# PERIPHERALS.net
KiCad netlist of a schematic drawn in Altium Designer
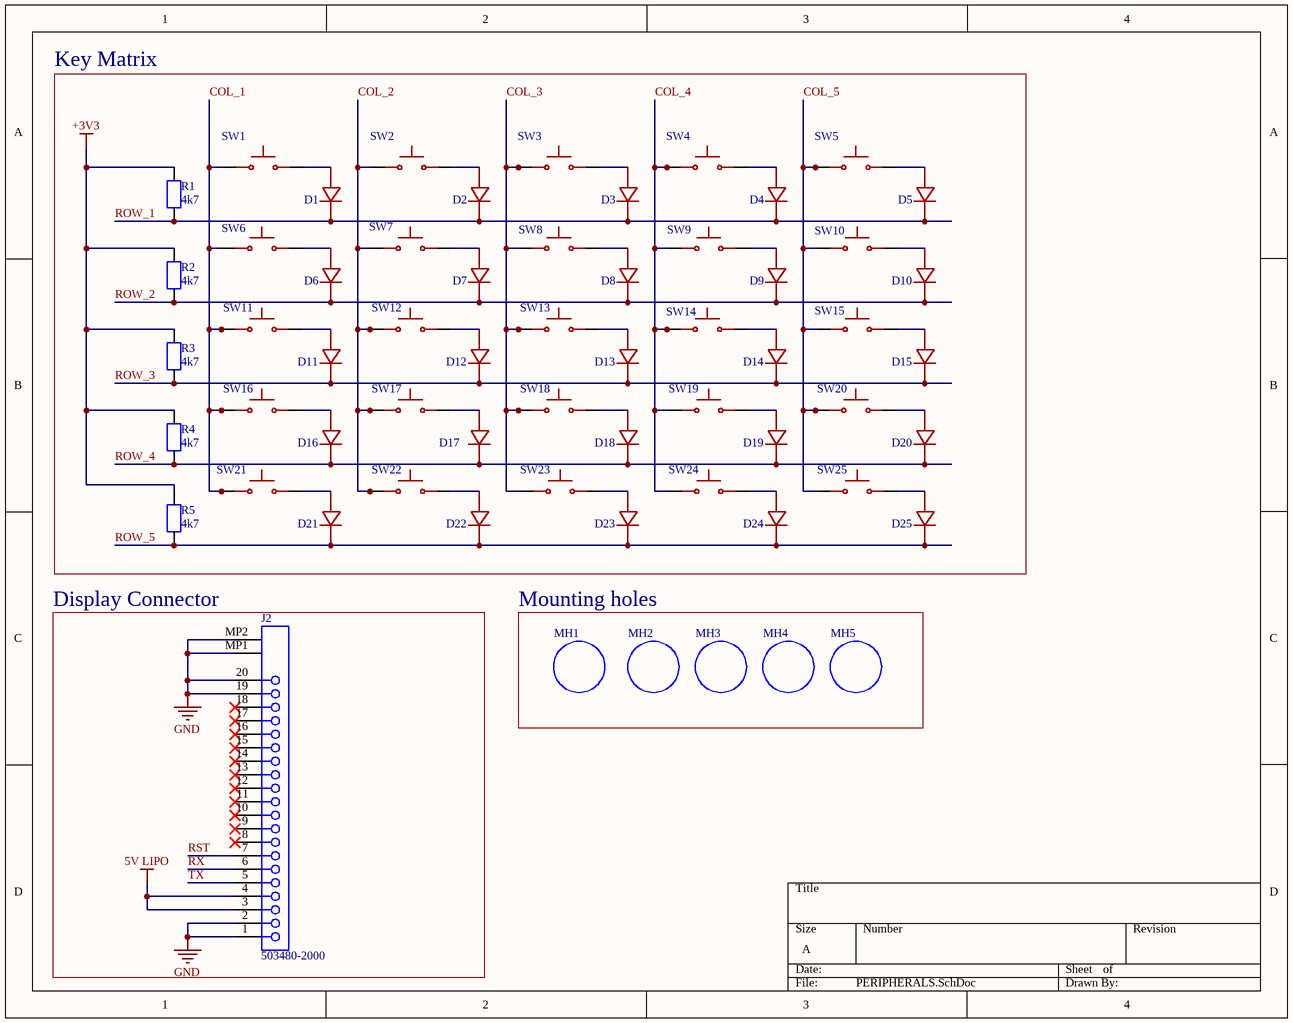
[diagram p0: PERIPHERALS.SchDoc]

(export (version "E")
  (design (tool "Eeschema 10.0.6"))
  (components
    (comp (ref "D1")
      (value "SOD-323")
      (footprint "SOD-323")
      (description "1N4148WS")
      (libsource (lib "schematiclibrary") (part "SOD-323"))
    )
    (comp (ref "D2")
      (value "SOD-323")
      (footprint "SOD-323")
      (description "1N4148WS")
      (libsource (lib "schematiclibrary") (part "SOD-323"))
    )
    (comp (ref "D3")
      (value "SOD-323")
      (footprint "SOD-323")
      (description "1N4148WS")
      (libsource (lib "schematiclibrary") (part "SOD-323"))
    )
    (comp (ref "D4")
      (value "SOD-323")
      (footprint "SOD-323")
      (description "1N4148WS")
      (libsource (lib "schematiclibrary") (part "SOD-323"))
    )
    (comp (ref "D5")
      (value "SOD-323")
      (footprint "SOD-323")
      (description "1N4148WS")
      (libsource (lib "schematiclibrary") (part "SOD-323"))
    )
    (comp (ref "D6")
      (value "SOD-323")
      (footprint "SOD-323")
      (description "1N4148WS")
      (libsource (lib "schematiclibrary") (part "SOD-323"))
    )
    (comp (ref "D7")
      (value "SOD-323")
      (footprint "SOD-323")
      (description "1N4148WS")
      (libsource (lib "schematiclibrary") (part "SOD-323"))
    )
    (comp (ref "D8")
      (value "SOD-323")
      (footprint "SOD-323")
      (description "1N4148WS")
      (libsource (lib "schematiclibrary") (part "SOD-323"))
    )
    (comp (ref "D9")
      (value "SOD-323")
      (footprint "SOD-323")
      (description "1N4148WS")
      (libsource (lib "schematiclibrary") (part "SOD-323"))
    )
    (comp (ref "D10")
      (value "SOD-323")
      (footprint "SOD-323")
      (description "1N4148WS")
      (libsource (lib "schematiclibrary") (part "SOD-323"))
    )
    (comp (ref "D11")
      (value "SOD-323")
      (footprint "SOD-323")
      (description "1N4148WS")
      (libsource (lib "schematiclibrary") (part "SOD-323"))
    )
    (comp (ref "D12")
      (value "SOD-323")
      (footprint "SOD-323")
      (description "1N4148WS")
      (libsource (lib "schematiclibrary") (part "SOD-323"))
    )
    (comp (ref "D13")
      (value "SOD-323")
      (footprint "SOD-323")
      (description "1N4148WS")
      (libsource (lib "schematiclibrary") (part "SOD-323"))
    )
    (comp (ref "D14")
      (value "SOD-323")
      (footprint "SOD-323")
      (description "1N4148WS")
      (libsource (lib "schematiclibrary") (part "SOD-323"))
    )
    (comp (ref "D15")
      (value "SOD-323")
      (footprint "SOD-323")
      (description "1N4148WS")
      (libsource (lib "schematiclibrary") (part "SOD-323"))
    )
    (comp (ref "D16")
      (value "SOD-323")
      (footprint "SOD-323")
      (description "1N4148WS")
      (libsource (lib "schematiclibrary") (part "SOD-323"))
    )
    (comp (ref "D17")
      (value "SOD-323")
      (footprint "SOD-323")
      (description "1N4148WS")
      (libsource (lib "schematiclibrary") (part "SOD-323"))
    )
    (comp (ref "D18")
      (value "SOD-323")
      (footprint "SOD-323")
      (description "1N4148WS")
      (libsource (lib "schematiclibrary") (part "SOD-323"))
    )
    (comp (ref "D19")
      (value "SOD-323")
      (footprint "SOD-323")
      (description "1N4148WS")
      (libsource (lib "schematiclibrary") (part "SOD-323"))
    )
    (comp (ref "D20")
      (value "SOD-323")
      (footprint "SOD-323")
      (description "1N4148WS")
      (libsource (lib "schematiclibrary") (part "SOD-323"))
    )
    (comp (ref "D21")
      (value "SOD-323")
      (footprint "SOD-323")
      (description "1N4148WS")
      (libsource (lib "schematiclibrary") (part "SOD-323"))
    )
    (comp (ref "D22")
      (value "SOD-323")
      (footprint "SOD-323")
      (description "1N4148WS")
      (libsource (lib "schematiclibrary") (part "SOD-323"))
    )
    (comp (ref "D23")
      (value "SOD-323")
      (footprint "SOD-323")
      (description "1N4148WS")
      (libsource (lib "schematiclibrary") (part "SOD-323"))
    )
    (comp (ref "D24")
      (value "SOD-323")
      (footprint "SOD-323")
      (description "1N4148WS")
      (libsource (lib "schematiclibrary") (part "SOD-323"))
    )
    (comp (ref "D25")
      (value "SOD-323")
      (footprint "SOD-323")
      (description "1N4148WS")
      (libsource (lib "schematiclibrary") (part "SOD-323"))
    )
    (comp (ref "J2")
      (value "503480-2000")
      (footprint "MOLX-503480-2000")
      (fields (field (name "MANUFACTURER") "Molex"))
      (libsource (lib "Altium Content Vault") (part "MOLX-503480-2000"))
    )
    (comp (ref "MH1")
      (value "m2 mounting hole")
      (footprint "m2 mounting hole")
      (libsource (lib "schematiclibrary") (part "m2 mounting hole"))
    )
    (comp (ref "MH2")
      (value "m2 mounting hole")
      (footprint "m2 mounting hole")
      (libsource (lib "schematiclibrary") (part "m2 mounting hole"))
    )
    (comp (ref "MH3")
      (value "m2 mounting hole")
      (footprint "m2 mounting hole")
      (libsource (lib "schematiclibrary") (part "m2 mounting hole"))
    )
    (comp (ref "MH4")
      (value "m2 mounting hole")
      (footprint "m2 mounting hole")
      (libsource (lib "schematiclibrary") (part "m2 mounting hole"))
    )
    (comp (ref "MH5")
      (value "m2 mounting hole")
      (footprint "m2 mounting hole")
      (libsource (lib "schematiclibrary") (part "m2 mounting hole"))
    )
    (comp (ref "R1")
      (value "4k7")
      (footprint "0603 resistor")
      (libsource (lib "schematiclibrary") (part "0603 resistor"))
    )
    (comp (ref "R2")
      (value "4k7")
      (footprint "0603 resistor")
      (libsource (lib "schematiclibrary") (part "0603 resistor"))
    )
    (comp (ref "R3")
      (value "4k7")
      (footprint "0603 resistor")
      (libsource (lib "schematiclibrary") (part "0603 resistor"))
    )
    (comp (ref "R4")
      (value "4k7")
      (footprint "0603 resistor")
      (libsource (lib "schematiclibrary") (part "0603 resistor"))
    )
    (comp (ref "R5")
      (value "4k7")
      (footprint "0603 resistor")
      (libsource (lib "schematiclibrary") (part "0603 resistor"))
    )
    (comp (ref "SW1")
      (value "switch")
      (footprint "chocv1")
      (libsource (lib "schematiclibrary") (part "switch"))
    )
    (comp (ref "SW2")
      (value "switch")
      (footprint "chocv1")
      (libsource (lib "schematiclibrary") (part "switch"))
    )
    (comp (ref "SW3")
      (value "switch")
      (footprint "chocv1")
      (libsource (lib "schematiclibrary") (part "switch"))
    )
    (comp (ref "SW4")
      (value "switch")
      (footprint "chocv1")
      (libsource (lib "schematiclibrary") (part "switch"))
    )
    (comp (ref "SW5")
      (value "switch")
      (footprint "chocv1")
      (libsource (lib "schematiclibrary") (part "switch"))
    )
    (comp (ref "SW6")
      (value "switch")
      (footprint "chocv1")
      (libsource (lib "schematiclibrary") (part "switch"))
    )
    (comp (ref "SW7")
      (value "switch")
      (footprint "chocv1")
      (libsource (lib "schematiclibrary") (part "switch"))
    )
    (comp (ref "SW8")
      (value "switch")
      (footprint "chocv1")
      (libsource (lib "schematiclibrary") (part "switch"))
    )
    (comp (ref "SW9")
      (value "switch")
      (footprint "chocv1")
      (libsource (lib "schematiclibrary") (part "switch"))
    )
    (comp (ref "SW10")
      (value "switch")
      (footprint "chocv1")
      (libsource (lib "schematiclibrary") (part "switch"))
    )
    (comp (ref "SW11")
      (value "switch")
      (footprint "chocv1")
      (libsource (lib "schematiclibrary") (part "switch"))
    )
    (comp (ref "SW12")
      (value "switch")
      (footprint "chocv1")
      (libsource (lib "schematiclibrary") (part "switch"))
    )
    (comp (ref "SW13")
      (value "switch")
      (footprint "chocv1")
      (libsource (lib "schematiclibrary") (part "switch"))
    )
    (comp (ref "SW14")
      (value "switch")
      (footprint "chocv1")
      (libsource (lib "schematiclibrary") (part "switch"))
    )
    (comp (ref "SW15")
      (value "switch")
      (footprint "chocv1")
      (libsource (lib "schematiclibrary") (part "switch"))
    )
    (comp (ref "SW16")
      (value "switch")
      (footprint "chocv1")
      (libsource (lib "schematiclibrary") (part "switch"))
    )
    (comp (ref "SW17")
      (value "switch")
      (footprint "chocv1")
      (libsource (lib "schematiclibrary") (part "switch"))
    )
    (comp (ref "SW18")
      (value "switch")
      (footprint "chocv1")
      (libsource (lib "schematiclibrary") (part "switch"))
    )
    (comp (ref "SW19")
      (value "switch")
      (footprint "chocv1")
      (libsource (lib "schematiclibrary") (part "switch"))
    )
    (comp (ref "SW20")
      (value "switch")
      (footprint "chocv1")
      (libsource (lib "schematiclibrary") (part "switch"))
    )
    (comp (ref "SW21")
      (value "switch")
      (footprint "chocv1")
      (libsource (lib "schematiclibrary") (part "switch"))
    )
    (comp (ref "SW22")
      (value "switch")
      (footprint "chocv1")
      (libsource (lib "schematiclibrary") (part "switch"))
    )
    (comp (ref "SW23")
      (value "switch")
      (footprint "chocv1")
      (libsource (lib "schematiclibrary") (part "switch"))
    )
    (comp (ref "SW24")
      (value "switch")
      (footprint "chocv1")
      (libsource (lib "schematiclibrary") (part "switch"))
    )
    (comp (ref "SW25")
      (value "switch")
      (footprint "chocv1")
      (libsource (lib "schematiclibrary") (part "switch"))
    )
  )
  (nets
    (net (code "1") (name "+3V3") (class "Default")
      (node (ref "R1") (pin "2") (pinfunction "12_2") (pintype "passive"))
      (node (ref "R2") (pin "2") (pinfunction "12_2") (pintype "passive"))
      (node (ref "R3") (pin "2") (pinfunction "12_2") (pintype "passive"))
      (node (ref "R4") (pin "2") (pinfunction "12_2") (pintype "passive"))
      (node (ref "R5") (pin "2") (pinfunction "12_2") (pintype "passive"))
    )
    (net (code "2") (name "/COL_1") (class "Default")
      (node (ref "SW1") (pin "2") (pinfunction "2_2") (pintype "passive"))
      (node (ref "SW11") (pin "2") (pinfunction "2_2") (pintype "passive"))
      (node (ref "SW16") (pin "2") (pinfunction "2_2") (pintype "passive"))
      (node (ref "SW21") (pin "2") (pinfunction "2_2") (pintype "passive"))
      (node (ref "SW6") (pin "2") (pinfunction "2_2") (pintype "passive"))
    )
    (net (code "3") (name "/COL_2") (class "Default")
      (node (ref "SW12") (pin "2") (pinfunction "2_2") (pintype "passive"))
      (node (ref "SW17") (pin "2") (pinfunction "2_2") (pintype "passive"))
      (node (ref "SW2") (pin "2") (pinfunction "2_2") (pintype "passive"))
      (node (ref "SW22") (pin "2") (pinfunction "2_2") (pintype "passive"))
      (node (ref "SW7") (pin "2") (pinfunction "2_2") (pintype "passive"))
    )
    (net (code "4") (name "/COL_3") (class "Default")
      (node (ref "SW13") (pin "2") (pinfunction "2_2") (pintype "passive"))
      (node (ref "SW18") (pin "2") (pinfunction "2_2") (pintype "passive"))
      (node (ref "SW23") (pin "2") (pinfunction "2_2") (pintype "passive"))
      (node (ref "SW3") (pin "2") (pinfunction "2_2") (pintype "passive"))
      (node (ref "SW8") (pin "2") (pinfunction "2_2") (pintype "passive"))
    )
    (net (code "5") (name "/COL_4") (class "Default")
      (node (ref "SW14") (pin "2") (pinfunction "2_2") (pintype "passive"))
      (node (ref "SW19") (pin "2") (pinfunction "2_2") (pintype "passive"))
      (node (ref "SW24") (pin "2") (pinfunction "2_2") (pintype "passive"))
      (node (ref "SW4") (pin "2") (pinfunction "2_2") (pintype "passive"))
      (node (ref "SW9") (pin "2") (pinfunction "2_2") (pintype "passive"))
    )
    (net (code "6") (name "/COL_5") (class "Default")
      (node (ref "SW10") (pin "2") (pinfunction "2_2") (pintype "passive"))
      (node (ref "SW15") (pin "2") (pinfunction "2_2") (pintype "passive"))
      (node (ref "SW20") (pin "2") (pinfunction "2_2") (pintype "passive"))
      (node (ref "SW25") (pin "2") (pinfunction "2_2") (pintype "passive"))
      (node (ref "SW5") (pin "2") (pinfunction "2_2") (pintype "passive"))
    )
    (net (code "7") (name "/ROW_1") (class "Default")
      (node (ref "D1") (pin "1") (pinfunction "C_1") (pintype "passive"))
      (node (ref "D2") (pin "1") (pinfunction "C_1") (pintype "passive"))
      (node (ref "D3") (pin "1") (pinfunction "C_1") (pintype "passive"))
      (node (ref "D4") (pin "1") (pinfunction "C_1") (pintype "passive"))
      (node (ref "D5") (pin "1") (pinfunction "C_1") (pintype "passive"))
      (node (ref "R1") (pin "1") (pinfunction "11_1") (pintype "passive"))
    )
    (net (code "8") (name "/ROW_2") (class "Default")
      (node (ref "D10") (pin "1") (pinfunction "C_1") (pintype "passive"))
      (node (ref "D6") (pin "1") (pinfunction "C_1") (pintype "passive"))
      (node (ref "D7") (pin "1") (pinfunction "C_1") (pintype "passive"))
      (node (ref "D8") (pin "1") (pinfunction "C_1") (pintype "passive"))
      (node (ref "D9") (pin "1") (pinfunction "C_1") (pintype "passive"))
      (node (ref "R2") (pin "1") (pinfunction "11_1") (pintype "passive"))
    )
    (net (code "9") (name "/ROW_3") (class "Default")
      (node (ref "D11") (pin "1") (pinfunction "C_1") (pintype "passive"))
      (node (ref "D12") (pin "1") (pinfunction "C_1") (pintype "passive"))
      (node (ref "D13") (pin "1") (pinfunction "C_1") (pintype "passive"))
      (node (ref "D14") (pin "1") (pinfunction "C_1") (pintype "passive"))
      (node (ref "D15") (pin "1") (pinfunction "C_1") (pintype "passive"))
      (node (ref "R3") (pin "1") (pinfunction "11_1") (pintype "passive"))
    )
    (net (code "10") (name "/ROW_4") (class "Default")
      (node (ref "D16") (pin "1") (pinfunction "C_1") (pintype "passive"))
      (node (ref "D17") (pin "1") (pinfunction "C_1") (pintype "passive"))
      (node (ref "D18") (pin "1") (pinfunction "C_1") (pintype "passive"))
      (node (ref "D19") (pin "1") (pinfunction "C_1") (pintype "passive"))
      (node (ref "D20") (pin "1") (pinfunction "C_1") (pintype "passive"))
      (node (ref "R4") (pin "1") (pinfunction "11_1") (pintype "passive"))
    )
    (net (code "11") (name "/ROW_5") (class "Default")
      (node (ref "D21") (pin "1") (pinfunction "C_1") (pintype "passive"))
      (node (ref "D22") (pin "1") (pinfunction "C_1") (pintype "passive"))
      (node (ref "D23") (pin "1") (pinfunction "C_1") (pintype "passive"))
      (node (ref "D24") (pin "1") (pinfunction "C_1") (pintype "passive"))
      (node (ref "D25") (pin "1") (pinfunction "C_1") (pintype "passive"))
      (node (ref "R5") (pin "1") (pinfunction "11_1") (pintype "passive"))
    )
    (net (code "12") (name "/RST") (class "Default")
      (node (ref "J2") (pin "7") (pinfunction "7_7") (pintype "passive"))
    )
    (net (code "13") (name "/RX") (class "Default")
      (node (ref "J2") (pin "6") (pinfunction "6_6") (pintype "passive"))
    )
    (net (code "14") (name "/TX") (class "Default")
      (node (ref "J2") (pin "5") (pinfunction "5_5") (pintype "passive"))
    )
    (net (code "15") (name "5V LIPO") (class "Default")
      (node (ref "J2") (pin "3") (pinfunction "3_3") (pintype "passive"))
      (node (ref "J2") (pin "4") (pinfunction "4_4") (pintype "passive"))
    )
    (net (code "16") (name "GND") (class "Default")
      (node (ref "J2") (pin "1") (pinfunction "1_1") (pintype "passive"))
      (node (ref "J2") (pin "19") (pinfunction "19_19") (pintype "passive"))
      (node (ref "J2") (pin "2") (pinfunction "2_2") (pintype "passive"))
      (node (ref "J2") (pin "20") (pinfunction "20_20") (pintype "passive"))
      (node (ref "J2") (pin "MP1") (pinfunction "MP1_MP1") (pintype "passive"))
      (node (ref "J2") (pin "MP2") (pinfunction "MP2_MP2") (pintype "passive"))
    )
    (net (code "17") (name "Net-(D1-A)") (class "Default")
      (node (ref "D1") (pin "2") (pinfunction "A_2") (pintype "passive"))
      (node (ref "SW1") (pin "1") (pinfunction "1_1") (pintype "passive"))
    )
    (net (code "18") (name "Net-(D2-A)") (class "Default")
      (node (ref "D2") (pin "2") (pinfunction "A_2") (pintype "passive"))
      (node (ref "SW2") (pin "1") (pinfunction "1_1") (pintype "passive"))
    )
    (net (code "19") (name "Net-(D3-A)") (class "Default")
      (node (ref "D3") (pin "2") (pinfunction "A_2") (pintype "passive"))
      (node (ref "SW3") (pin "1") (pinfunction "1_1") (pintype "passive"))
    )
    (net (code "20") (name "Net-(D4-A)") (class "Default")
      (node (ref "D4") (pin "2") (pinfunction "A_2") (pintype "passive"))
      (node (ref "SW4") (pin "1") (pinfunction "1_1") (pintype "passive"))
    )
    (net (code "21") (name "Net-(D5-A)") (class "Default")
      (node (ref "D5") (pin "2") (pinfunction "A_2") (pintype "passive"))
      (node (ref "SW5") (pin "1") (pinfunction "1_1") (pintype "passive"))
    )
    (net (code "22") (name "Net-(D6-A)") (class "Default")
      (node (ref "D6") (pin "2") (pinfunction "A_2") (pintype "passive"))
      (node (ref "SW6") (pin "1") (pinfunction "1_1") (pintype "passive"))
    )
    (net (code "23") (name "Net-(D7-A)") (class "Default")
      (node (ref "D7") (pin "2") (pinfunction "A_2") (pintype "passive"))
      (node (ref "SW7") (pin "1") (pinfunction "1_1") (pintype "passive"))
    )
    (net (code "24") (name "Net-(D8-A)") (class "Default")
      (node (ref "D8") (pin "2") (pinfunction "A_2") (pintype "passive"))
      (node (ref "SW8") (pin "1") (pinfunction "1_1") (pintype "passive"))
    )
    (net (code "25") (name "Net-(D9-A)") (class "Default")
      (node (ref "D9") (pin "2") (pinfunction "A_2") (pintype "passive"))
      (node (ref "SW9") (pin "1") (pinfunction "1_1") (pintype "passive"))
    )
    (net (code "26") (name "Net-(D10-A)") (class "Default")
      (node (ref "D10") (pin "2") (pinfunction "A_2") (pintype "passive"))
      (node (ref "SW10") (pin "1") (pinfunction "1_1") (pintype "passive"))
    )
    (net (code "27") (name "Net-(D11-A)") (class "Default")
      (node (ref "D11") (pin "2") (pinfunction "A_2") (pintype "passive"))
      (node (ref "SW11") (pin "1") (pinfunction "1_1") (pintype "passive"))
    )
    (net (code "28") (name "Net-(D12-A)") (class "Default")
      (node (ref "D12") (pin "2") (pinfunction "A_2") (pintype "passive"))
      (node (ref "SW12") (pin "1") (pinfunction "1_1") (pintype "passive"))
    )
    (net (code "29") (name "Net-(D13-A)") (class "Default")
      (node (ref "D13") (pin "2") (pinfunction "A_2") (pintype "passive"))
      (node (ref "SW13") (pin "1") (pinfunction "1_1") (pintype "passive"))
    )
    (net (code "30") (name "Net-(D14-A)") (class "Default")
      (node (ref "D14") (pin "2") (pinfunction "A_2") (pintype "passive"))
      (node (ref "SW14") (pin "1") (pinfunction "1_1") (pintype "passive"))
    )
    (net (code "31") (name "Net-(D15-A)") (class "Default")
      (node (ref "D15") (pin "2") (pinfunction "A_2") (pintype "passive"))
      (node (ref "SW15") (pin "1") (pinfunction "1_1") (pintype "passive"))
    )
    (net (code "32") (name "Net-(D16-A)") (class "Default")
      (node (ref "D16") (pin "2") (pinfunction "A_2") (pintype "passive"))
      (node (ref "SW16") (pin "1") (pinfunction "1_1") (pintype "passive"))
    )
    (net (code "33") (name "Net-(D17-A)") (class "Default")
      (node (ref "D17") (pin "2") (pinfunction "A_2") (pintype "passive"))
      (node (ref "SW17") (pin "1") (pinfunction "1_1") (pintype "passive"))
    )
    (net (code "34") (name "Net-(D18-A)") (class "Default")
      (node (ref "D18") (pin "2") (pinfunction "A_2") (pintype "passive"))
      (node (ref "SW18") (pin "1") (pinfunction "1_1") (pintype "passive"))
    )
    (net (code "35") (name "Net-(D19-A)") (class "Default")
      (node (ref "D19") (pin "2") (pinfunction "A_2") (pintype "passive"))
      (node (ref "SW19") (pin "1") (pinfunction "1_1") (pintype "passive"))
    )
    (net (code "36") (name "Net-(D20-A)") (class "Default")
      (node (ref "D20") (pin "2") (pinfunction "A_2") (pintype "passive"))
      (node (ref "SW20") (pin "1") (pinfunction "1_1") (pintype "passive"))
    )
    (net (code "37") (name "Net-(D21-A)") (class "Default")
      (node (ref "D21") (pin "2") (pinfunction "A_2") (pintype "passive"))
      (node (ref "SW21") (pin "1") (pinfunction "1_1") (pintype "passive"))
    )
    (net (code "38") (name "Net-(D22-A)") (class "Default")
      (node (ref "D22") (pin "2") (pinfunction "A_2") (pintype "passive"))
      (node (ref "SW22") (pin "1") (pinfunction "1_1") (pintype "passive"))
    )
    (net (code "39") (name "Net-(D23-A)") (class "Default")
      (node (ref "D23") (pin "2") (pinfunction "A_2") (pintype "passive"))
      (node (ref "SW23") (pin "1") (pinfunction "1_1") (pintype "passive"))
    )
    (net (code "40") (name "Net-(D24-A)") (class "Default")
      (node (ref "D24") (pin "2") (pinfunction "A_2") (pintype "passive"))
      (node (ref "SW24") (pin "1") (pinfunction "1_1") (pintype "passive"))
    )
    (net (code "41") (name "Net-(D25-A)") (class "Default")
      (node (ref "D25") (pin "2") (pinfunction "A_2") (pintype "passive"))
      (node (ref "SW25") (pin "1") (pinfunction "1_1") (pintype "passive"))
    )
    (net (code "42") (name "unconnected-(J2-Pad8)") (class "Default")
      (node (ref "J2") (pin "8") (pinfunction "8_8") (pintype "passive+no_connect"))
    )
    (net (code "43") (name "unconnected-(J2-Pad9)") (class "Default")
      (node (ref "J2") (pin "9") (pinfunction "9_9") (pintype "passive+no_connect"))
    )
    (net (code "44") (name "unconnected-(J2-Pad10)") (class "Default")
      (node (ref "J2") (pin "10") (pinfunction "10_10") (pintype "passive+no_connect"))
    )
    (net (code "45") (name "unconnected-(J2-Pad11)") (class "Default")
      (node (ref "J2") (pin "11") (pinfunction "11_11") (pintype "passive+no_connect"))
    )
    (net (code "46") (name "unconnected-(J2-Pad12)") (class "Default")
      (node (ref "J2") (pin "12") (pinfunction "12_12") (pintype "passive+no_connect"))
    )
    (net (code "47") (name "unconnected-(J2-Pad13)") (class "Default")
      (node (ref "J2") (pin "13") (pinfunction "13_13") (pintype "passive+no_connect"))
    )
    (net (code "48") (name "unconnected-(J2-Pad14)") (class "Default")
      (node (ref "J2") (pin "14") (pinfunction "14_14") (pintype "passive+no_connect"))
    )
    (net (code "49") (name "unconnected-(J2-Pad15)") (class "Default")
      (node (ref "J2") (pin "15") (pinfunction "15_15") (pintype "passive+no_connect"))
    )
    (net (code "50") (name "unconnected-(J2-Pad16)") (class "Default")
      (node (ref "J2") (pin "16") (pinfunction "16_16") (pintype "passive+no_connect"))
    )
    (net (code "51") (name "unconnected-(J2-Pad17)") (class "Default")
      (node (ref "J2") (pin "17") (pinfunction "17_17") (pintype "passive+no_connect"))
    )
    (net (code "52") (name "unconnected-(J2-Pad18)") (class "Default")
      (node (ref "J2") (pin "18") (pinfunction "18_18") (pintype "passive+no_connect"))
    )
  )
)
